# RS232-U5_U6.net
KiCad netlist of a schematic drawn in Altium Designer
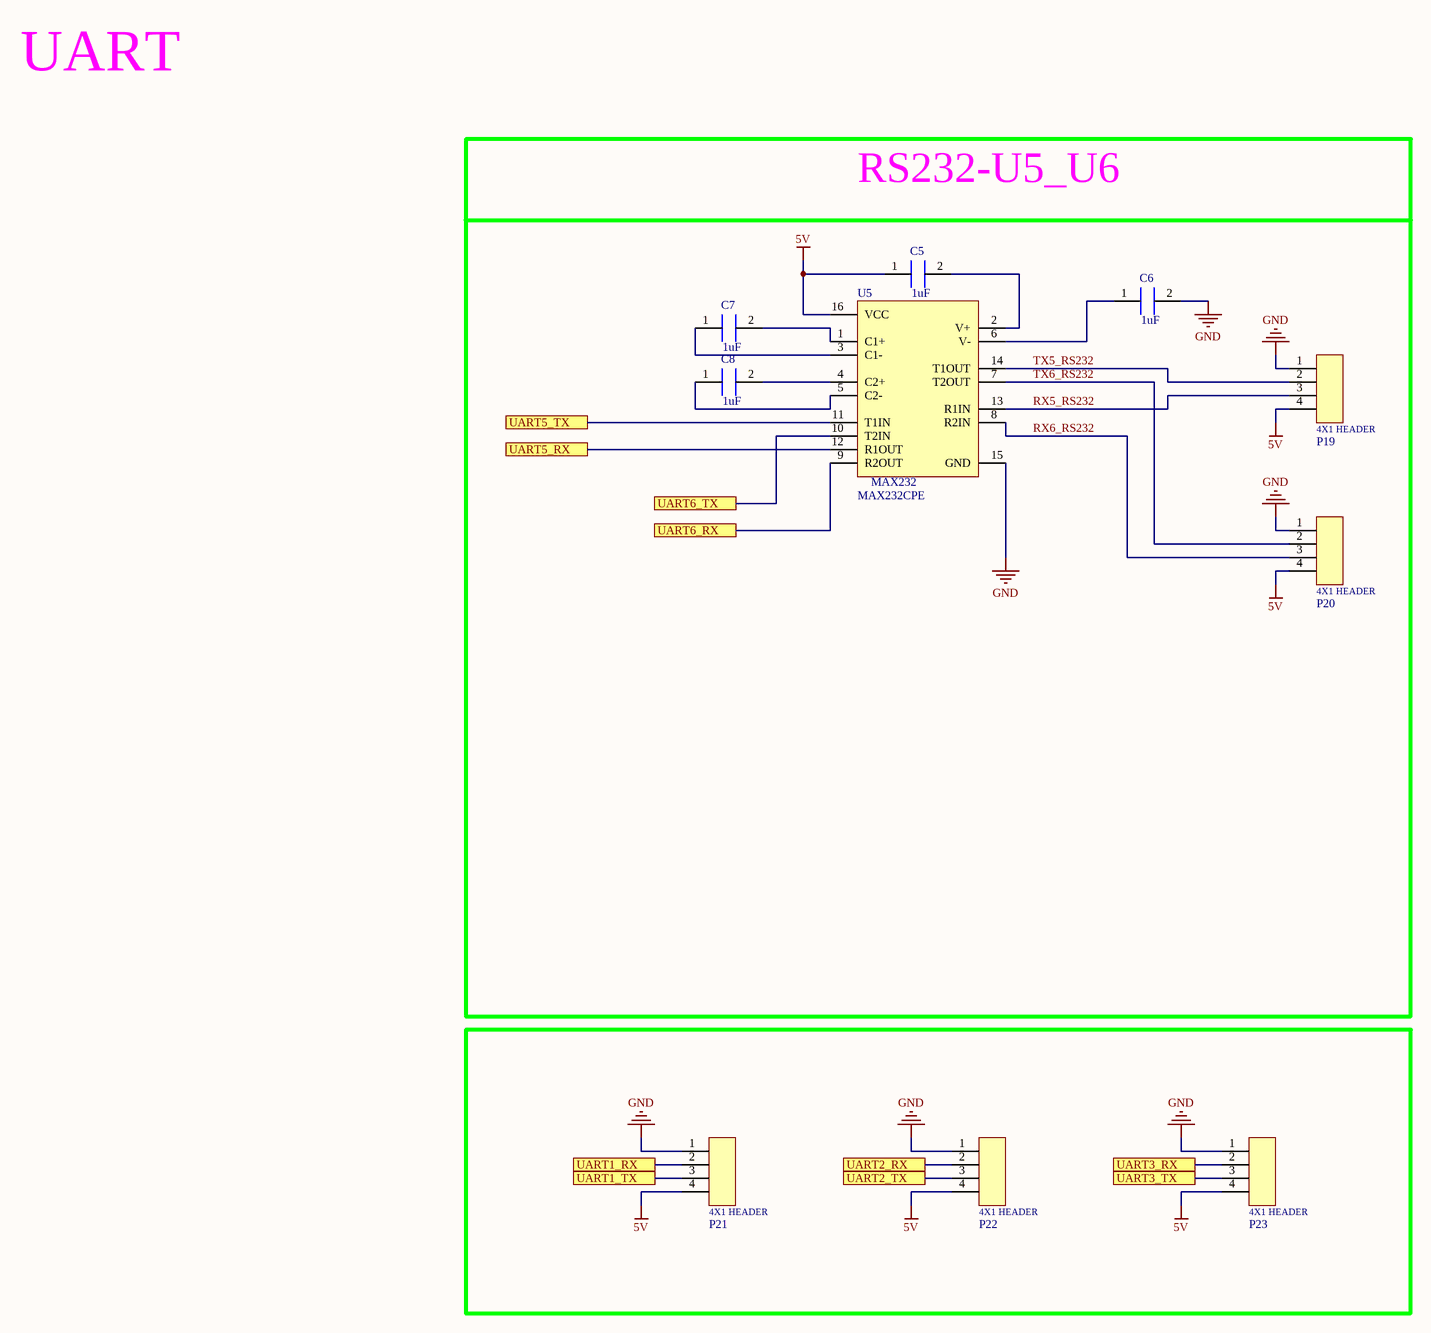
[diagram p0: RS232-U5_U6.SchDoc]

(export (version "E")
  (design (tool "Eeschema 10.0.6"))
  (components
    (comp (ref "C5")
      (value "CAP CER 1UF 25V X7R 0805")
      (footprint "C0805C105J3RAC7800")
      (description "Cap Ceramic 1uF 25V X7R 5% SMD 0805 125C Plastic T/R")
      (fields
        (field (name "MANUFACTURER") "KEMET")
        (field (name "MANUFACTURER PART NUMBER") "C0805C105J3RACTU")
      )
      (libsource (lib "Schlib1") (part "C0805C105J3RAC7800"))
    )
    (comp (ref "C6")
      (value "CAP CER 1UF 25V X7R 0805")
      (footprint "C0805C105J3RAC7800")
      (description "Cap Ceramic 1uF 25V X7R 5% SMD 0805 125C Plastic T/R")
      (fields
        (field (name "MANUFACTURER") "KEMET")
        (field (name "MANUFACTURER PART NUMBER") "C0805C105J3RACTU")
      )
      (libsource (lib "Schlib1") (part "C0805C105J3RAC7800"))
    )
    (comp (ref "C7")
      (value "CAP CER 1UF 25V X7R 0805")
      (footprint "C0805C105J3RAC7800")
      (description "Cap Ceramic 1uF 25V X7R 5% SMD 0805 125C Plastic T/R")
      (fields
        (field (name "MANUFACTURER") "KEMET")
        (field (name "MANUFACTURER PART NUMBER") "C0805C105J3RACTU")
      )
      (libsource (lib "Schlib1") (part "C0805C105J3RAC7800"))
    )
    (comp (ref "C8")
      (value "CAP CER 1UF 25V X7R 0805")
      (footprint "C0805C105J3RAC7800")
      (description "Cap Ceramic 1uF 25V X7R 5% SMD 0805 125C Plastic T/R")
      (fields
        (field (name "MANUFACTURER") "KEMET")
        (field (name "MANUFACTURER PART NUMBER") "C0805C105J3RACTU")
      )
      (libsource (lib "Schlib1") (part "C0805C105J3RAC7800"))
    )
    (comp (ref "P19")
      (value "WIRE-TO BOARD HEADER, 2.5MM, 4 C")
      (footprint "51125-04-0200-01")
      (description "Wire-to Board Header, 2.5MM, 4 C")
      (fields
        (field (name "MANUFACTURER") "CNC Tech")
        (field (name "MANUFACTURER PART NUMBER") "51125-04-0200-01")
      )
      (libsource (lib "Schlib1") (part "51125-04-0200-01"))
    )
    (comp (ref "P20")
      (value "WIRE-TO BOARD HEADER, 2.5MM, 4 C")
      (footprint "51125-04-0200-01")
      (description "Wire-to Board Header, 2.5MM, 4 C")
      (fields
        (field (name "MANUFACTURER") "CNC Tech")
        (field (name "MANUFACTURER PART NUMBER") "51125-04-0200-01")
      )
      (libsource (lib "Schlib1") (part "51125-04-0200-01"))
    )
    (comp (ref "P21")
      (value "WIRE-TO BOARD HEADER, 2.5MM, 4 C")
      (footprint "51125-04-0200-01")
      (description "Wire-to Board Header, 2.5MM, 4 C")
      (fields
        (field (name "MANUFACTURER") "CNC Tech")
        (field (name "MANUFACTURER PART NUMBER") "51125-04-0200-01")
      )
      (libsource (lib "Schlib1") (part "51125-04-0200-01"))
    )
    (comp (ref "P22")
      (value "WIRE-TO BOARD HEADER, 2.5MM, 4 C")
      (footprint "51125-04-0200-01")
      (description "Wire-to Board Header, 2.5MM, 4 C")
      (fields
        (field (name "MANUFACTURER") "CNC Tech")
        (field (name "MANUFACTURER PART NUMBER") "51125-04-0200-01")
      )
      (libsource (lib "Schlib1") (part "51125-04-0200-01"))
    )
    (comp (ref "P23")
      (value "WIRE-TO BOARD HEADER, 2.5MM, 4 C")
      (footprint "51125-04-0200-01")
      (description "Wire-to Board Header, 2.5MM, 4 C")
      (fields
        (field (name "MANUFACTURER") "CNC Tech")
        (field (name "MANUFACTURER PART NUMBER") "51125-04-0200-01")
      )
      (libsource (lib "Schlib1") (part "51125-04-0200-01"))
    )
    (comp (ref "U5")
      (value "MAX232CPE")
      (footprint "MAX232CPE")
      (description "MAX232 Series 120 kbps 5.5 V Through Hole RS-232 Transceiver - PDIP-16")
      (fields (field (name "MANUFACTURER") "Maxim") (field (name "MANUFACTURER PART NUMBER") "MAX232CPE+"))
      (libsource (lib "Schlib1") (part "MAX232CPE"))
    )
  )
  (nets
    (net (code "1") (name "/RX5_RS232") (class "Default")
      (node (ref "P19") (pin "3") (pinfunction "7_3") (pintype "passive"))
      (node (ref "U5") (pin "13") (pinfunction "R1IN_13") (pintype "passive"))
    )
    (net (code "2") (name "/RX6_RS232") (class "Default")
      (node (ref "P20") (pin "3") (pinfunction "7_3") (pintype "passive"))
      (node (ref "U5") (pin "8") (pinfunction "R2IN_8") (pintype "passive"))
    )
    (net (code "3") (name "/TX5_RS232") (class "Default")
      (node (ref "P19") (pin "2") (pinfunction "8_2") (pintype "passive"))
      (node (ref "U5") (pin "14") (pinfunction "T1OUT_14") (pintype "passive"))
    )
    (net (code "4") (name "/TX6_RS232") (class "Default")
      (node (ref "P20") (pin "2") (pinfunction "8_2") (pintype "passive"))
      (node (ref "U5") (pin "7") (pinfunction "T2OUT_7") (pintype "passive"))
    )
    (net (code "5") (name "/UART1_RX") (class "Default")
      (node (ref "P21") (pin "2") (pinfunction "8_2") (pintype "passive"))
    )
    (net (code "6") (name "/UART1_TX") (class "Default")
      (node (ref "P21") (pin "3") (pinfunction "7_3") (pintype "passive"))
    )
    (net (code "7") (name "/UART2_RX") (class "Default")
      (node (ref "P22") (pin "2") (pinfunction "8_2") (pintype "passive"))
    )
    (net (code "8") (name "/UART2_TX") (class "Default")
      (node (ref "P22") (pin "3") (pinfunction "7_3") (pintype "passive"))
    )
    (net (code "9") (name "/UART3_RX") (class "Default")
      (node (ref "P23") (pin "2") (pinfunction "8_2") (pintype "passive"))
    )
    (net (code "10") (name "/UART3_TX") (class "Default")
      (node (ref "P23") (pin "3") (pinfunction "7_3") (pintype "passive"))
    )
    (net (code "11") (name "/UART5_RX") (class "Default")
      (node (ref "U5") (pin "12") (pinfunction "R1OUT_12") (pintype "passive"))
    )
    (net (code "12") (name "/UART5_TX") (class "Default")
      (node (ref "U5") (pin "11") (pinfunction "T1IN_11") (pintype "passive"))
    )
    (net (code "13") (name "/UART6_RX") (class "Default")
      (node (ref "U5") (pin "9") (pinfunction "R2OUT_9") (pintype "passive"))
    )
    (net (code "14") (name "/UART6_TX") (class "Default")
      (node (ref "U5") (pin "10") (pinfunction "T2IN_10") (pintype "passive"))
    )
    (net (code "15") (name "5V") (class "Default")
      (node (ref "C5") (pin "1") (pintype "passive"))
      (node (ref "P19") (pin "4") (pinfunction "6_4") (pintype "passive"))
      (node (ref "P20") (pin "4") (pinfunction "6_4") (pintype "passive"))
      (node (ref "P21") (pin "4") (pinfunction "6_4") (pintype "passive"))
      (node (ref "P22") (pin "4") (pinfunction "6_4") (pintype "passive"))
      (node (ref "P23") (pin "4") (pinfunction "6_4") (pintype "passive"))
      (node (ref "U5") (pin "16") (pinfunction "VCC_16") (pintype "passive"))
    )
    (net (code "16") (name "GND") (class "Default")
      (node (ref "C6") (pin "2") (pintype "passive"))
      (node (ref "P19") (pin "1") (pintype "passive"))
      (node (ref "P20") (pin "1") (pintype "passive"))
      (node (ref "P21") (pin "1") (pintype "passive"))
      (node (ref "P22") (pin "1") (pintype "passive"))
      (node (ref "P23") (pin "1") (pintype "passive"))
      (node (ref "U5") (pin "15") (pinfunction "GND_15") (pintype "passive"))
    )
    (net (code "17") (name "Net-(U5-C1+)") (class "Default")
      (node (ref "C7") (pin "2") (pintype "passive"))
      (node (ref "U5") (pin "1") (pinfunction "C1+_1") (pintype "passive"))
    )
    (net (code "18") (name "Net-(U5-C1-)") (class "Default")
      (node (ref "C7") (pin "1") (pintype "passive"))
      (node (ref "U5") (pin "3") (pinfunction "C1-_3") (pintype "passive"))
    )
    (net (code "19") (name "Net-(U5-C2+)") (class "Default")
      (node (ref "C8") (pin "2") (pintype "passive"))
      (node (ref "U5") (pin "4") (pinfunction "C2+_4") (pintype "passive"))
    )
    (net (code "20") (name "Net-(U5-C2-)") (class "Default")
      (node (ref "C8") (pin "1") (pintype "passive"))
      (node (ref "U5") (pin "5") (pinfunction "C2-_5") (pintype "passive"))
    )
    (net (code "21") (name "Net-(U5-V+)") (class "Default")
      (node (ref "C5") (pin "2") (pintype "passive"))
      (node (ref "U5") (pin "2") (pinfunction "V+_2") (pintype "passive"))
    )
    (net (code "22") (name "Net-(U5-V-)") (class "Default")
      (node (ref "C6") (pin "1") (pintype "passive"))
      (node (ref "U5") (pin "6") (pinfunction "V-_6") (pintype "passive"))
    )
  )
)
